# breakout.net
KiCad netlist of a schematic drawn in EAGLE
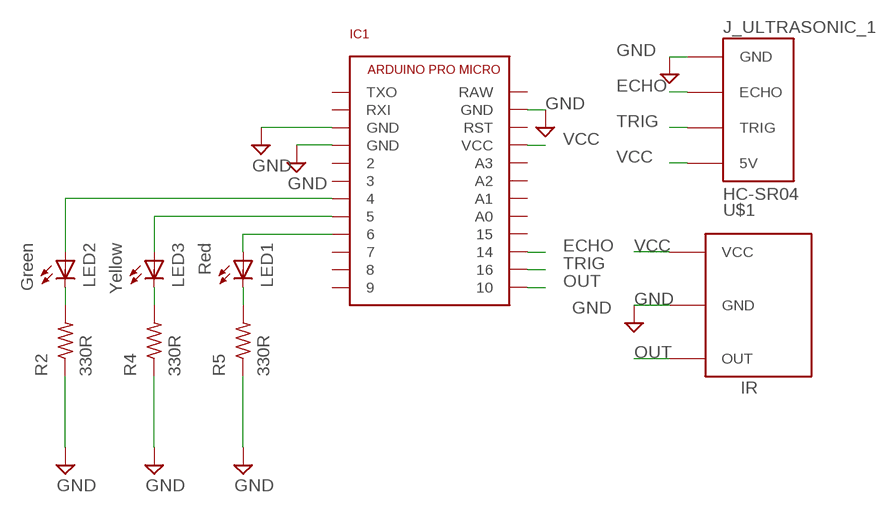
[diagram p0: schematic, sheet 1]

(export (version "E")
  (design (tool "Eeschema 10.0.6"))
  (components
    (comp (ref "IC1")
      (value "ARDUINO_PRO_MICRO")
      (footprint "eagle-import:ARDUINO_PRO_MICRO")
      (fields
        (field (name "DISTRIBUTOR_PART_NUMBER") "32284746884")
        (field (name "MANUFACTURER") "Feiyang electronics")
      )
      (libsource (lib "eagle-import") (part "ARDUINO_PRO_MICRO"))
    )
    (comp (ref "J_ULTRASONIC_1")
      (value "HC-SR04")
      (footprint "eagle-import:HC-SR04_FOOTPRINT")
      (libsource (lib "eagle-import") (part "HC-SR04"))
    )
    (comp (ref "LED1")
      (value "Red")
      (footprint "eagle-import:LED-0603")
      (fields
        (field (name "DISTRIBUTOR_PART_NUMBER") "160-1415-1-ND")
        (field (name "MANUFACTURER") "Lite-On Inc")
        (field (name "MANUFACTURER_PART_NUMBER") "LTST-C170KRKT")
      )
      (libsource (lib "eagle-import") (part "LED0603"))
    )
    (comp (ref "LED2")
      (value "Green")
      (footprint "eagle-import:LED-0603")
      (fields
        (field (name "DISTRIBUTOR_PART_NUMBER") "160-1415-1-ND")
        (field (name "MANUFACTURER") "Lite-On Inc")
        (field (name "MANUFACTURER_PART_NUMBER") "LTST-C170KRKT")
      )
      (libsource (lib "eagle-import") (part "LED0603"))
    )
    (comp (ref "LED3")
      (value "Yellow")
      (footprint "eagle-import:LED-0603")
      (fields
        (field (name "DISTRIBUTOR_PART_NUMBER") "160-1415-1-ND")
        (field (name "MANUFACTURER") "Lite-On Inc")
        (field (name "MANUFACTURER_PART_NUMBER") "LTST-C170KRKT")
      )
      (libsource (lib "eagle-import") (part "LED0603"))
    )
    (comp (ref "R2")
      (value "330R")
      (footprint "eagle-import:R0603")
      (fields (field (name "MANUFACTURER") "Rohm Semiconductor"))
      (libsource (lib "eagle-import") (part "R-US_R0603"))
    )
    (comp (ref "R4")
      (value "330R")
      (footprint "eagle-import:R0603")
      (fields (field (name "MANUFACTURER") "Rohm Semiconductor"))
      (libsource (lib "eagle-import") (part "R-US_R0603"))
    )
    (comp (ref "R5")
      (value "330R")
      (footprint "eagle-import:R0603")
      (fields (field (name "MANUFACTURER") "Rohm Semiconductor"))
      (libsource (lib "eagle-import") (part "R-US_R0603"))
    )
    (comp (ref "U$1")
      (value "IR")
      (footprint "eagle-import:1X03")
      (libsource (lib "eagle-import") (part "IR"))
    )
  )
  (nets
    (net (code "1") (name "/ECHO") (class "Default")
      (node (ref "IC1") (pin "14") (pinfunction "14_14") (pintype "bidirectional"))
      (node (ref "J_ULTRASONIC_1") (pin "ECHO") (pinfunction "ECHO_ECHO") (pintype "bidirectional"))
    )
    (net (code "2") (name "/OUT") (class "Default")
      (node (ref "IC1") (pin "10") (pinfunction "10_10") (pintype "bidirectional"))
      (node (ref "U$1") (pin "3") (pinfunction "OUT_3") (pintype "bidirectional"))
    )
    (net (code "3") (name "/TRIG") (class "Default")
      (node (ref "IC1") (pin "16") (pinfunction "16_16") (pintype "bidirectional"))
      (node (ref "J_ULTRASONIC_1") (pin "TRIG") (pinfunction "TRIG_TRIG") (pintype "bidirectional"))
    )
    (net (code "4") (name "/VCC") (class "Default")
      (node (ref "IC1") (pin "VCC") (pinfunction "VCC_VCC") (pintype "bidirectional"))
      (node (ref "J_ULTRASONIC_1") (pin "VCC") (pinfunction "5V_VCC") (pintype "bidirectional"))
      (node (ref "U$1") (pin "1") (pinfunction "VCC_1") (pintype "bidirectional"))
    )
    (net (code "5") (name "GND") (class "Default")
      (node (ref "IC1") (pin "GND@0") (pinfunction "GND_GND@0") (pintype "bidirectional"))
      (node (ref "IC1") (pin "GND@1") (pinfunction "GND_GND@1") (pintype "bidirectional"))
      (node (ref "IC1") (pin "GND@2") (pinfunction "GND_GND@2") (pintype "bidirectional"))
      (node (ref "J_ULTRASONIC_1") (pin "GND") (pinfunction "GND_GND") (pintype "bidirectional"))
      (node (ref "R2") (pin "1") (pinfunction "1_1") (pintype "passive"))
      (node (ref "R4") (pin "1") (pinfunction "1_1") (pintype "passive"))
      (node (ref "R5") (pin "1") (pinfunction "1_1") (pintype "passive"))
      (node (ref "U$1") (pin "2") (pinfunction "GND_2") (pintype "bidirectional"))
    )
    (net (code "6") (name "Net-(IC1-Pad4)") (class "Default")
      (node (ref "IC1") (pin "4") (pinfunction "4_4") (pintype "bidirectional"))
      (node (ref "LED2") (pin "A") (pinfunction "A_A") (pintype "passive"))
    )
    (net (code "7") (name "Net-(IC1-Pad5)") (class "Default")
      (node (ref "IC1") (pin "5") (pinfunction "5_5") (pintype "bidirectional"))
      (node (ref "LED3") (pin "A") (pinfunction "A_A") (pintype "passive"))
    )
    (net (code "8") (name "Net-(IC1-Pad6)") (class "Default")
      (node (ref "IC1") (pin "6") (pinfunction "6_6") (pintype "bidirectional"))
      (node (ref "LED1") (pin "A") (pinfunction "A_A") (pintype "passive"))
    )
    (net (code "9") (name "Net-(LED1-PadC)") (class "Default")
      (node (ref "LED1") (pin "C") (pinfunction "C_C") (pintype "passive"))
      (node (ref "R5") (pin "2") (pinfunction "2_2") (pintype "passive"))
    )
    (net (code "10") (name "Net-(LED2-PadC)") (class "Default")
      (node (ref "LED2") (pin "C") (pinfunction "C_C") (pintype "passive"))
      (node (ref "R2") (pin "2") (pinfunction "2_2") (pintype "passive"))
    )
    (net (code "11") (name "Net-(LED3-PadC)") (class "Default")
      (node (ref "LED3") (pin "C") (pinfunction "C_C") (pintype "passive"))
      (node (ref "R4") (pin "2") (pinfunction "2_2") (pintype "passive"))
    )
    (net (code "12") (name "unconnected-(IC1-Pad2)") (class "Default")
      (node (ref "IC1") (pin "2") (pinfunction "2_2") (pintype "bidirectional"))
    )
    (net (code "13") (name "unconnected-(IC1-Pad3)") (class "Default")
      (node (ref "IC1") (pin "3") (pinfunction "3_3") (pintype "bidirectional"))
    )
    (net (code "14") (name "unconnected-(IC1-Pad7)") (class "Default")
      (node (ref "IC1") (pin "7") (pinfunction "7_7") (pintype "bidirectional"))
    )
    (net (code "15") (name "unconnected-(IC1-Pad8)") (class "Default")
      (node (ref "IC1") (pin "8") (pinfunction "8_8") (pintype "bidirectional"))
    )
    (net (code "16") (name "unconnected-(IC1-Pad9)") (class "Default")
      (node (ref "IC1") (pin "9") (pinfunction "9_9") (pintype "bidirectional"))
    )
    (net (code "17") (name "unconnected-(IC1-Pad15)") (class "Default")
      (node (ref "IC1") (pin "15") (pinfunction "15_15") (pintype "bidirectional"))
    )
    (net (code "18") (name "unconnected-(IC1-PadA0)") (class "Default")
      (node (ref "IC1") (pin "A0") (pinfunction "A0_A0") (pintype "bidirectional"))
    )
    (net (code "19") (name "unconnected-(IC1-PadA1)") (class "Default")
      (node (ref "IC1") (pin "A1") (pinfunction "A1_A1") (pintype "bidirectional"))
    )
    (net (code "20") (name "unconnected-(IC1-PadA2)") (class "Default")
      (node (ref "IC1") (pin "A2") (pinfunction "A2_A2") (pintype "bidirectional"))
    )
    (net (code "21") (name "unconnected-(IC1-PadA3)") (class "Default")
      (node (ref "IC1") (pin "A3") (pinfunction "A3_A3") (pintype "bidirectional"))
    )
    (net (code "22") (name "unconnected-(IC1-PadRAW)") (class "Default")
      (node (ref "IC1") (pin "RAW") (pinfunction "RAW_RAW") (pintype "bidirectional"))
    )
    (net (code "23") (name "unconnected-(IC1-PadRST)") (class "Default")
      (node (ref "IC1") (pin "RST") (pinfunction "RST_RST") (pintype "bidirectional"))
    )
    (net (code "24") (name "unconnected-(IC1-PadRXI)") (class "Default")
      (node (ref "IC1") (pin "RXI") (pinfunction "RXI_RXI") (pintype "bidirectional"))
    )
    (net (code "25") (name "unconnected-(IC1-PadTXO)") (class "Default")
      (node (ref "IC1") (pin "TXO") (pinfunction "TXO_TXO") (pintype "bidirectional"))
    )
  )
)
